# Test_Points.net
KiCad netlist of a schematic drawn in Altium Designer
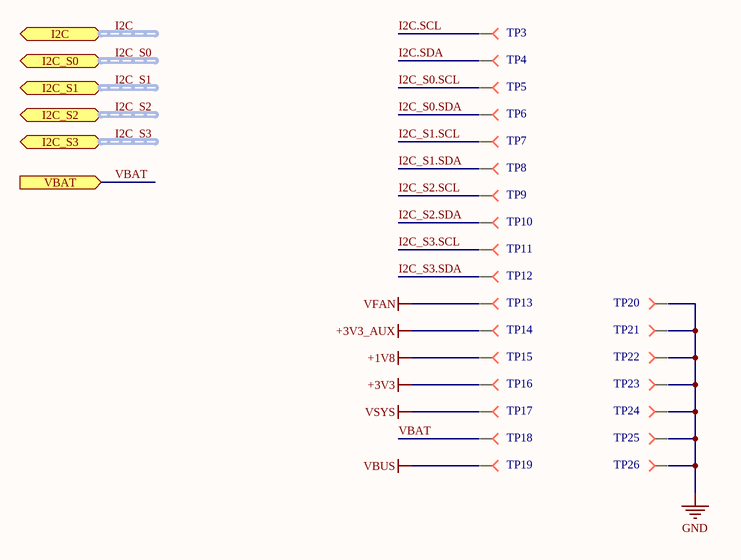
[diagram p0: Test_Points.SchDoc]

(export (version "E")
  (design (tool "Eeschema 10.0.6"))
  (components
    (comp (ref "TP3")
      (value "Test Point Pad")
      (footprint "Testpoint")
      (description "Test Point. There is nothing to buy or mount.")
      (libsource (lib "BLDC_Motor_Driver") (part "Test Point Pad"))
    )
    (comp (ref "TP4")
      (value "Test Point Pad")
      (footprint "Testpoint")
      (description "Test Point. There is nothing to buy or mount.")
      (libsource (lib "BLDC_Motor_Driver") (part "Test Point Pad"))
    )
    (comp (ref "TP5")
      (value "Test Point Pad")
      (footprint "Testpoint")
      (description "Test Point. There is nothing to buy or mount.")
      (libsource (lib "BLDC_Motor_Driver") (part "Test Point Pad"))
    )
    (comp (ref "TP6")
      (value "Test Point Pad")
      (footprint "Testpoint")
      (description "Test Point. There is nothing to buy or mount.")
      (libsource (lib "BLDC_Motor_Driver") (part "Test Point Pad"))
    )
    (comp (ref "TP7")
      (value "Test Point Pad")
      (footprint "Testpoint")
      (description "Test Point. There is nothing to buy or mount.")
      (libsource (lib "BLDC_Motor_Driver") (part "Test Point Pad"))
    )
    (comp (ref "TP8")
      (value "Test Point Pad")
      (footprint "Testpoint")
      (description "Test Point. There is nothing to buy or mount.")
      (libsource (lib "BLDC_Motor_Driver") (part "Test Point Pad"))
    )
    (comp (ref "TP9")
      (value "Test Point Pad")
      (footprint "Testpoint")
      (description "Test Point. There is nothing to buy or mount.")
      (libsource (lib "BLDC_Motor_Driver") (part "Test Point Pad"))
    )
    (comp (ref "TP10")
      (value "Test Point Pad")
      (footprint "Testpoint")
      (description "Test Point. There is nothing to buy or mount.")
      (libsource (lib "BLDC_Motor_Driver") (part "Test Point Pad"))
    )
    (comp (ref "TP11")
      (value "Test Point Pad")
      (footprint "Testpoint")
      (description "Test Point. There is nothing to buy or mount.")
      (libsource (lib "BLDC_Motor_Driver") (part "Test Point Pad"))
    )
    (comp (ref "TP12")
      (value "Test Point Pad")
      (footprint "Testpoint")
      (description "Test Point. There is nothing to buy or mount.")
      (libsource (lib "BLDC_Motor_Driver") (part "Test Point Pad"))
    )
    (comp (ref "TP13")
      (value "Test Point Pad")
      (footprint "Testpoint")
      (description "Test Point. There is nothing to buy or mount.")
      (libsource (lib "BLDC_Motor_Driver") (part "Test Point Pad"))
    )
    (comp (ref "TP14")
      (value "Test Point Pad")
      (footprint "Testpoint")
      (description "Test Point. There is nothing to buy or mount.")
      (libsource (lib "BLDC_Motor_Driver") (part "Test Point Pad"))
    )
    (comp (ref "TP15")
      (value "Test Point Pad")
      (footprint "Testpoint")
      (description "Test Point. There is nothing to buy or mount.")
      (libsource (lib "BLDC_Motor_Driver") (part "Test Point Pad"))
    )
    (comp (ref "TP16")
      (value "Test Point Pad")
      (footprint "Testpoint")
      (description "Test Point. There is nothing to buy or mount.")
      (libsource (lib "BLDC_Motor_Driver") (part "Test Point Pad"))
    )
    (comp (ref "TP17")
      (value "Test Point Pad")
      (footprint "Testpoint")
      (description "Test Point. There is nothing to buy or mount.")
      (libsource (lib "BLDC_Motor_Driver") (part "Test Point Pad"))
    )
    (comp (ref "TP18")
      (value "Test Point Pad")
      (footprint "Testpoint")
      (description "Test Point. There is nothing to buy or mount.")
      (libsource (lib "BLDC_Motor_Driver") (part "Test Point Pad"))
    )
    (comp (ref "TP19")
      (value "Test Point Pad")
      (footprint "Testpoint")
      (description "Test Point. There is nothing to buy or mount.")
      (libsource (lib "BLDC_Motor_Driver") (part "Test Point Pad"))
    )
    (comp (ref "TP20")
      (value "Test Point Pad")
      (footprint "Testpoint")
      (description "Test Point. There is nothing to buy or mount.")
      (libsource (lib "") (part "Test Point Pad_1"))
    )
    (comp (ref "TP21")
      (value "Test Point Pad")
      (footprint "Testpoint")
      (description "Test Point. There is nothing to buy or mount.")
      (libsource (lib "") (part "Test Point Pad_1"))
    )
    (comp (ref "TP22")
      (value "Test Point Pad")
      (footprint "Testpoint")
      (description "Test Point. There is nothing to buy or mount.")
      (libsource (lib "") (part "Test Point Pad_1"))
    )
    (comp (ref "TP23")
      (value "Test Point Pad")
      (footprint "Testpoint")
      (description "Test Point. There is nothing to buy or mount.")
      (libsource (lib "") (part "Test Point Pad_1"))
    )
    (comp (ref "TP24")
      (value "Test Point Pad")
      (footprint "Testpoint")
      (description "Test Point. There is nothing to buy or mount.")
      (libsource (lib "") (part "Test Point Pad_1"))
    )
    (comp (ref "TP25")
      (value "Test Point Pad")
      (footprint "Testpoint")
      (description "Test Point. There is nothing to buy or mount.")
      (libsource (lib "") (part "Test Point Pad_1"))
    )
    (comp (ref "TP26")
      (value "Test Point Pad")
      (footprint "Testpoint")
      (description "Test Point. There is nothing to buy or mount.")
      (libsource (lib "") (part "Test Point Pad_1"))
    )
  )
  (nets
    (net (code "6") (name "+1V8") (class "Default")
      (node (ref "TP15") (pin "1") (pinfunction "1_1") (pintype "passive"))
    )
    (net (code "7") (name "+3V3") (class "Default")
      (node (ref "TP16") (pin "1") (pinfunction "1_1") (pintype "passive"))
    )
    (net (code "8") (name "+3V3_AUX") (class "Default")
      (node (ref "TP14") (pin "1") (pinfunction "1_1") (pintype "passive"))
    )
    (net (code "9") (name "/I2C.SCL") (class "Default")
      (node (ref "TP3") (pin "1") (pinfunction "1_1") (pintype "passive"))
    )
    (net (code "10") (name "/I2C.SDA") (class "Default")
      (node (ref "TP4") (pin "1") (pinfunction "1_1") (pintype "passive"))
    )
    (net (code "11") (name "/I2C_S0.SCL") (class "Default")
      (node (ref "TP5") (pin "1") (pinfunction "1_1") (pintype "passive"))
    )
    (net (code "12") (name "/I2C_S0.SDA") (class "Default")
      (node (ref "TP6") (pin "1") (pinfunction "1_1") (pintype "passive"))
    )
    (net (code "13") (name "/I2C_S1.SCL") (class "Default")
      (node (ref "TP7") (pin "1") (pinfunction "1_1") (pintype "passive"))
    )
    (net (code "14") (name "/I2C_S1.SDA") (class "Default")
      (node (ref "TP8") (pin "1") (pinfunction "1_1") (pintype "passive"))
    )
    (net (code "15") (name "/I2C_S2.SCL") (class "Default")
      (node (ref "TP9") (pin "1") (pinfunction "1_1") (pintype "passive"))
    )
    (net (code "16") (name "/I2C_S2.SDA") (class "Default")
      (node (ref "TP10") (pin "1") (pinfunction "1_1") (pintype "passive"))
    )
    (net (code "17") (name "/I2C_S3.SCL") (class "Default")
      (node (ref "TP11") (pin "1") (pinfunction "1_1") (pintype "passive"))
    )
    (net (code "18") (name "/I2C_S3.SDA") (class "Default")
      (node (ref "TP12") (pin "1") (pinfunction "1_1") (pintype "passive"))
    )
    (net (code "19") (name "/VBAT") (class "Default")
      (node (ref "TP18") (pin "1") (pinfunction "1_1") (pintype "passive"))
    )
    (net (code "25") (name "GND") (class "Default")
      (node (ref "TP20") (pin "1") (pinfunction "1_1") (pintype "passive"))
      (node (ref "TP21") (pin "1") (pinfunction "1_1") (pintype "passive"))
      (node (ref "TP22") (pin "1") (pinfunction "1_1") (pintype "passive"))
      (node (ref "TP23") (pin "1") (pinfunction "1_1") (pintype "passive"))
      (node (ref "TP24") (pin "1") (pinfunction "1_1") (pintype "passive"))
      (node (ref "TP25") (pin "1") (pinfunction "1_1") (pintype "passive"))
      (node (ref "TP26") (pin "1") (pinfunction "1_1") (pintype "passive"))
    )
    (net (code "26") (name "VBUS") (class "Default")
      (node (ref "TP19") (pin "1") (pinfunction "1_1") (pintype "passive"))
    )
    (net (code "27") (name "VFAN") (class "Default")
      (node (ref "TP13") (pin "1") (pinfunction "1_1") (pintype "passive"))
    )
    (net (code "28") (name "VSYS") (class "Default")
      (node (ref "TP17") (pin "1") (pinfunction "1_1") (pintype "passive"))
    )
  )
)
